# ImpactSensor.net
KiCad netlist of a schematic drawn in EAGLE
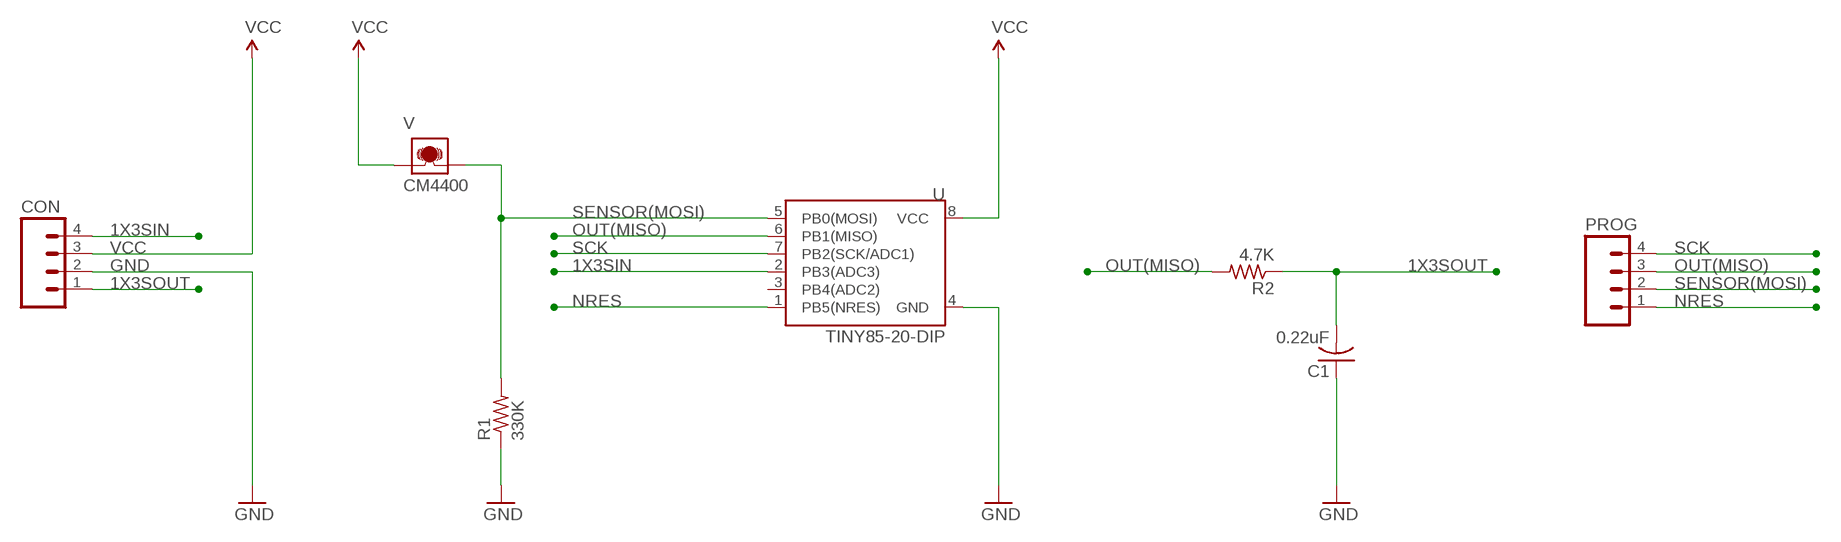
[diagram p0: schematic, sheet 1]

(export (version "E")
  (design (tool "Eeschema 10.0.6"))
  (components
    (comp (ref "C1")
      (value "0.22uF")
      (footprint "eagle-import:C0402")
      (libsource (lib "eagle-import") (part "C-USC0402"))
    )
    (comp (ref "CON")
      (value "M04PTH")
      (footprint "eagle-import:1X04")
      (libsource (lib "eagle-import") (part "M04PTH"))
    )
    (comp (ref "PROG")
      (value "M04PTH")
      (footprint "eagle-import:1X04")
      (libsource (lib "eagle-import") (part "M04PTH"))
    )
    (comp (ref "R1")
      (value "330K")
      (footprint "eagle-import:R0603")
      (libsource (lib "eagle-import") (part "R-US_R0603"))
    )
    (comp (ref "R2")
      (value "4.7K")
      (footprint "eagle-import:R0603")
      (libsource (lib "eagle-import") (part "R-US_R0603"))
    )
    (comp (ref "U")
      (value "TINY85-20-DIP")
      (footprint "eagle-import:DIP08")
      (libsource (lib "eagle-import") (part "ATTINY45TINY85-20-DIP"))
    )
    (comp (ref "V")
      (value "CM4400")
      (footprint "eagle-import:CM4400")
      (fields (field (name "MF") "FARNELL") (field (name "MPN") "CM4400-1."))
      (libsource (lib "eagle-import") (part "CM4400"))
    )
  )
  (nets
    (net (code "1") (name "/1X3SIN") (class "Default")
      (node (ref "CON") (pin "4") (pinfunction "4_4") (pintype "passive"))
      (node (ref "U") (pin "2") (pinfunction "PB3(ADC3)_2") (pintype "bidirectional"))
    )
    (net (code "2") (name "/1X3SOUT") (class "Default")
      (node (ref "C1") (pin "2") (pinfunction "2_2") (pintype "passive"))
      (node (ref "CON") (pin "1") (pinfunction "1_1") (pintype "passive"))
      (node (ref "R2") (pin "1") (pinfunction "1_1") (pintype "passive"))
    )
    (net (code "3") (name "/NRES") (class "Default")
      (node (ref "PROG") (pin "1") (pinfunction "1_1") (pintype "passive"))
      (node (ref "U") (pin "1") (pinfunction "PB5(NRES)_1") (pintype "bidirectional"))
    )
    (net (code "4") (name "/OUT(MISO)") (class "Default")
      (node (ref "PROG") (pin "3") (pinfunction "3_3") (pintype "passive"))
      (node (ref "R2") (pin "2") (pinfunction "2_2") (pintype "passive"))
      (node (ref "U") (pin "6") (pinfunction "PB1(MISO)_6") (pintype "bidirectional"))
    )
    (net (code "5") (name "/SCK") (class "Default")
      (node (ref "PROG") (pin "4") (pinfunction "4_4") (pintype "passive"))
      (node (ref "U") (pin "7") (pinfunction "PB2(SCK/ADC1)_7") (pintype "bidirectional"))
    )
    (net (code "6") (name "/SENSOR(MOSI)") (class "Default")
      (node (ref "PROG") (pin "2") (pinfunction "2_2") (pintype "passive"))
      (node (ref "R1") (pin "2") (pinfunction "2_2") (pintype "passive"))
      (node (ref "U") (pin "5") (pinfunction "PB0(MOSI)_5") (pintype "bidirectional"))
      (node (ref "V") (pin "2") (pinfunction "2_2") (pintype "passive"))
    )
    (net (code "7") (name "GND") (class "Default")
      (node (ref "C1") (pin "1") (pinfunction "1_1") (pintype "passive"))
      (node (ref "CON") (pin "2") (pinfunction "2_2") (pintype "passive"))
      (node (ref "R1") (pin "1") (pinfunction "1_1") (pintype "passive"))
      (node (ref "U") (pin "4") (pinfunction "GND_4") (pintype "bidirectional"))
    )
    (net (code "8") (name "VCC") (class "Default")
      (node (ref "CON") (pin "3") (pinfunction "3_3") (pintype "passive"))
      (node (ref "U") (pin "8") (pinfunction "VCC_8") (pintype "bidirectional"))
      (node (ref "V") (pin "1") (pinfunction "1_1") (pintype "passive"))
    )
    (net (code "9") (name "unconnected-(U-PB4(ADC2)-Pad3)") (class "Default")
      (node (ref "U") (pin "3") (pinfunction "PB4(ADC2)_3") (pintype "bidirectional"))
    )
  )
)
